# Li-Fi_Transmitter_Schematic.net
KiCad netlist of a schematic drawn in EAGLE
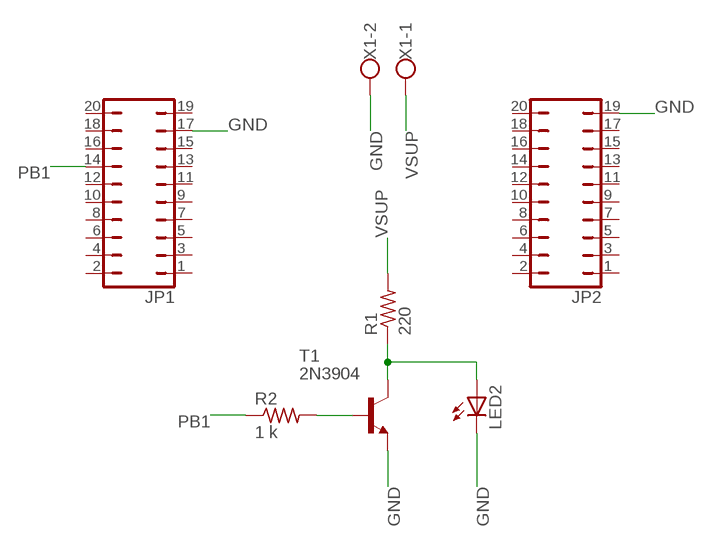
[diagram p0: schematic, sheet 1]

(export (version "E")
  (design (tool "Eeschema 10.0.6"))
  (components
    (comp (ref "JP1")
      (value "JP10Q")
      (footprint "eagle-import:JP10Q")
      (libsource (lib "eagle-import") (part "JP10Q"))
    )
    (comp (ref "JP2")
      (value "JP10Q")
      (footprint "eagle-import:JP10Q")
      (libsource (lib "eagle-import") (part "JP10Q"))
    )
    (comp (ref "LED2")
      (value "LEDKA-3528ASYC")
      (footprint "eagle-import:KA-3528ASYC")
      (libsource (lib "eagle-import") (part "LEDKA-3528ASYC"))
    )
    (comp (ref "R1")
      (value "220")
      (footprint "eagle-import:R0805")
      (libsource (lib "eagle-import") (part "R-US_R0805"))
    )
    (comp (ref "R2")
      (value "1 k")
      (footprint "eagle-import:R0805")
      (libsource (lib "eagle-import") (part "R-US_R0805"))
    )
    (comp (ref "T1")
      (value "2N3904")
      (footprint "eagle-import:TO92")
      (libsource (lib "eagle-import") (part "2N3904"))
    )
    (comp (ref "X1")
      (value "W237-102")
      (footprint "eagle-import:W237-102")
      (fields (field (name "MPN") "237-102"))
      (libsource (lib "eagle-import") (part "W237-102"))
    )
  )
  (nets
    (net (code "1") (name "/GND") (class "Default")
      (node (ref "JP1") (pin "17") (pinfunction "17_17") (pintype "passive"))
      (node (ref "JP2") (pin "19") (pinfunction "19_19") (pintype "passive"))
      (node (ref "LED2") (pin "C") (pinfunction "C_C") (pintype "passive"))
      (node (ref "T1") (pin "3") (pinfunction "E_3") (pintype "passive"))
      (node (ref "X1") (pin "2") (pinfunction "KL_2") (pintype "passive"))
    )
    (net (code "2") (name "/PB1") (class "Default")
      (node (ref "JP1") (pin "14") (pinfunction "14_14") (pintype "passive"))
      (node (ref "R2") (pin "1") (pinfunction "1_1") (pintype "passive"))
    )
    (net (code "3") (name "/VSUP") (class "Default")
      (node (ref "R1") (pin "2") (pinfunction "2_2") (pintype "passive"))
      (node (ref "X1") (pin "1") (pinfunction "KL_1") (pintype "passive"))
    )
    (net (code "4") (name "Net-(T1-B)") (class "Default")
      (node (ref "R2") (pin "2") (pinfunction "2_2") (pintype "passive"))
      (node (ref "T1") (pin "2") (pinfunction "B_2") (pintype "passive"))
    )
    (net (code "5") (name "Net-(T1-C)") (class "Default")
      (node (ref "LED2") (pin "A") (pinfunction "A_A") (pintype "passive"))
      (node (ref "R1") (pin "1") (pinfunction "1_1") (pintype "passive"))
      (node (ref "T1") (pin "1") (pinfunction "C_1") (pintype "passive"))
    )
    (net (code "6") (name "unconnected-(JP1-Pad1)") (class "Default")
      (node (ref "JP1") (pin "1") (pinfunction "1_1") (pintype "passive"))
    )
    (net (code "7") (name "unconnected-(JP1-Pad2)") (class "Default")
      (node (ref "JP1") (pin "2") (pinfunction "2_2") (pintype "passive"))
    )
    (net (code "8") (name "unconnected-(JP1-Pad3)") (class "Default")
      (node (ref "JP1") (pin "3") (pinfunction "3_3") (pintype "passive"))
    )
    (net (code "9") (name "unconnected-(JP1-Pad4)") (class "Default")
      (node (ref "JP1") (pin "4") (pinfunction "4_4") (pintype "passive"))
    )
    (net (code "10") (name "unconnected-(JP1-Pad5)") (class "Default")
      (node (ref "JP1") (pin "5") (pinfunction "5_5") (pintype "passive"))
    )
    (net (code "11") (name "unconnected-(JP1-Pad6)") (class "Default")
      (node (ref "JP1") (pin "6") (pinfunction "6_6") (pintype "passive"))
    )
    (net (code "12") (name "unconnected-(JP1-Pad7)") (class "Default")
      (node (ref "JP1") (pin "7") (pinfunction "7_7") (pintype "passive"))
    )
    (net (code "13") (name "unconnected-(JP1-Pad8)") (class "Default")
      (node (ref "JP1") (pin "8") (pinfunction "8_8") (pintype "passive"))
    )
    (net (code "14") (name "unconnected-(JP1-Pad9)") (class "Default")
      (node (ref "JP1") (pin "9") (pinfunction "9_9") (pintype "passive"))
    )
    (net (code "15") (name "unconnected-(JP1-Pad10)") (class "Default")
      (node (ref "JP1") (pin "10") (pinfunction "10_10") (pintype "passive"))
    )
    (net (code "16") (name "unconnected-(JP1-Pad11)") (class "Default")
      (node (ref "JP1") (pin "11") (pinfunction "11_11") (pintype "passive"))
    )
    (net (code "17") (name "unconnected-(JP1-Pad12)") (class "Default")
      (node (ref "JP1") (pin "12") (pinfunction "12_12") (pintype "passive"))
    )
    (net (code "18") (name "unconnected-(JP1-Pad13)") (class "Default")
      (node (ref "JP1") (pin "13") (pinfunction "13_13") (pintype "passive"))
    )
    (net (code "19") (name "unconnected-(JP1-Pad15)") (class "Default")
      (node (ref "JP1") (pin "15") (pinfunction "15_15") (pintype "passive"))
    )
    (net (code "20") (name "unconnected-(JP1-Pad16)") (class "Default")
      (node (ref "JP1") (pin "16") (pinfunction "16_16") (pintype "passive"))
    )
    (net (code "21") (name "unconnected-(JP1-Pad18)") (class "Default")
      (node (ref "JP1") (pin "18") (pinfunction "18_18") (pintype "passive"))
    )
    (net (code "22") (name "unconnected-(JP1-Pad19)") (class "Default")
      (node (ref "JP1") (pin "19") (pinfunction "19_19") (pintype "passive"))
    )
    (net (code "23") (name "unconnected-(JP1-Pad20)") (class "Default")
      (node (ref "JP1") (pin "20") (pinfunction "20_20") (pintype "passive"))
    )
    (net (code "24") (name "unconnected-(JP2-Pad1)") (class "Default")
      (node (ref "JP2") (pin "1") (pinfunction "1_1") (pintype "passive"))
    )
    (net (code "25") (name "unconnected-(JP2-Pad2)") (class "Default")
      (node (ref "JP2") (pin "2") (pinfunction "2_2") (pintype "passive"))
    )
    (net (code "26") (name "unconnected-(JP2-Pad3)") (class "Default")
      (node (ref "JP2") (pin "3") (pinfunction "3_3") (pintype "passive"))
    )
    (net (code "27") (name "unconnected-(JP2-Pad4)") (class "Default")
      (node (ref "JP2") (pin "4") (pinfunction "4_4") (pintype "passive"))
    )
    (net (code "28") (name "unconnected-(JP2-Pad5)") (class "Default")
      (node (ref "JP2") (pin "5") (pinfunction "5_5") (pintype "passive"))
    )
    (net (code "29") (name "unconnected-(JP2-Pad6)") (class "Default")
      (node (ref "JP2") (pin "6") (pinfunction "6_6") (pintype "passive"))
    )
    (net (code "30") (name "unconnected-(JP2-Pad7)") (class "Default")
      (node (ref "JP2") (pin "7") (pinfunction "7_7") (pintype "passive"))
    )
    (net (code "31") (name "unconnected-(JP2-Pad8)") (class "Default")
      (node (ref "JP2") (pin "8") (pinfunction "8_8") (pintype "passive"))
    )
    (net (code "32") (name "unconnected-(JP2-Pad9)") (class "Default")
      (node (ref "JP2") (pin "9") (pinfunction "9_9") (pintype "passive"))
    )
    (net (code "33") (name "unconnected-(JP2-Pad10)") (class "Default")
      (node (ref "JP2") (pin "10") (pinfunction "10_10") (pintype "passive"))
    )
    (net (code "34") (name "unconnected-(JP2-Pad11)") (class "Default")
      (node (ref "JP2") (pin "11") (pinfunction "11_11") (pintype "passive"))
    )
    (net (code "35") (name "unconnected-(JP2-Pad12)") (class "Default")
      (node (ref "JP2") (pin "12") (pinfunction "12_12") (pintype "passive"))
    )
    (net (code "36") (name "unconnected-(JP2-Pad13)") (class "Default")
      (node (ref "JP2") (pin "13") (pinfunction "13_13") (pintype "passive"))
    )
    (net (code "37") (name "unconnected-(JP2-Pad14)") (class "Default")
      (node (ref "JP2") (pin "14") (pinfunction "14_14") (pintype "passive"))
    )
    (net (code "38") (name "unconnected-(JP2-Pad15)") (class "Default")
      (node (ref "JP2") (pin "15") (pinfunction "15_15") (pintype "passive"))
    )
    (net (code "39") (name "unconnected-(JP2-Pad16)") (class "Default")
      (node (ref "JP2") (pin "16") (pinfunction "16_16") (pintype "passive"))
    )
    (net (code "40") (name "unconnected-(JP2-Pad17)") (class "Default")
      (node (ref "JP2") (pin "17") (pinfunction "17_17") (pintype "passive"))
    )
    (net (code "41") (name "unconnected-(JP2-Pad18)") (class "Default")
      (node (ref "JP2") (pin "18") (pinfunction "18_18") (pintype "passive"))
    )
    (net (code "42") (name "unconnected-(JP2-Pad20)") (class "Default")
      (node (ref "JP2") (pin "20") (pinfunction "20_20") (pintype "passive"))
    )
  )
)
